# VS1063.net
KiCad netlist of a schematic drawn in Altium Designer
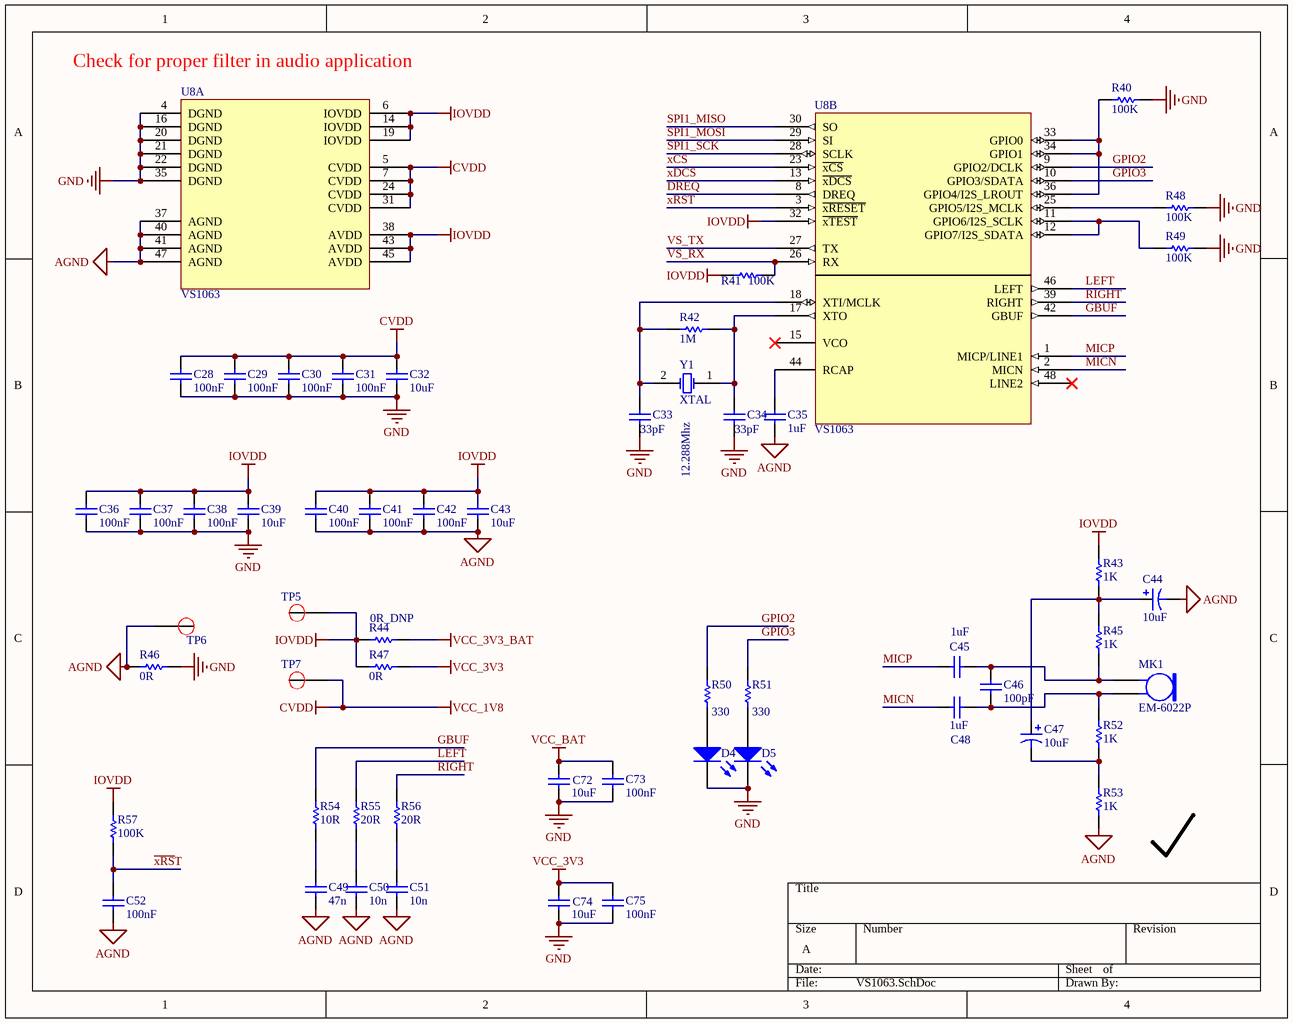
[diagram p0: VS1063.SchDoc]

(export (version "E")
  (design (tool "Eeschema 10.0.6"))
  (components
    (comp (ref "C28")
      (value "100nF")
      (footprint "0603PKG")
      (description "Capacitor (Semiconductor SIM Model)")
      (fields (field (name "Comment") "Cap Semi") (field (name "PUBLISHER") "Altium Limited"))
      (libsource (lib "Miscellaneous Devices") (part "Cap Semi"))
    )
    (comp (ref "C29")
      (value "100nF")
      (footprint "0603PKG")
      (description "Capacitor (Semiconductor SIM Model)")
      (fields (field (name "Comment") "Cap Semi") (field (name "PUBLISHER") "Altium Limited"))
      (libsource (lib "Miscellaneous Devices") (part "Cap Semi"))
    )
    (comp (ref "C30")
      (value "100nF")
      (footprint "0603PKG")
      (description "Capacitor (Semiconductor SIM Model)")
      (fields (field (name "Comment") "Cap Semi") (field (name "PUBLISHER") "Altium Limited"))
      (libsource (lib "Miscellaneous Devices") (part "Cap Semi"))
    )
    (comp (ref "C31")
      (value "100nF")
      (footprint "0603PKG")
      (description "Capacitor (Semiconductor SIM Model)")
      (fields (field (name "Comment") "Cap Semi") (field (name "PUBLISHER") "Altium Limited"))
      (libsource (lib "Miscellaneous Devices") (part "Cap Semi"))
    )
    (comp (ref "C32")
      (value "10uF")
      (footprint "0603PKG")
      (description "Capacitor (Semiconductor SIM Model)")
      (fields (field (name "Comment") "Cap Semi") (field (name "PUBLISHER") "Altium Limited"))
      (libsource (lib "Miscellaneous Devices") (part "Cap Semi"))
    )
    (comp (ref "C33")
      (value "33pF")
      (footprint "0603PKG")
      (description "Capacitor")
      (fields (field (name "Comment") "Cap") (field (name "PUBLISHER") "Altium Limited"))
      (libsource (lib "Miscellaneous Devices") (part "Cap"))
    )
    (comp (ref "C34")
      (value "33pF")
      (footprint "0603PKG")
      (description "Capacitor")
      (fields (field (name "Comment") "Cap") (field (name "PUBLISHER") "Altium Limited"))
      (libsource (lib "Miscellaneous Devices") (part "Cap"))
    )
    (comp (ref "C35")
      (value "1uF")
      (footprint "0603PKG")
      (description "Capacitor (Semiconductor SIM Model)")
      (fields (field (name "Comment") "Cap Semi") (field (name "PUBLISHER") "Altium Limited"))
      (libsource (lib "Miscellaneous Devices") (part "Cap Semi"))
    )
    (comp (ref "C36")
      (value "100nF")
      (footprint "0603PKG")
      (description "Capacitor (Semiconductor SIM Model)")
      (fields (field (name "Comment") "Cap Semi") (field (name "PUBLISHER") "Altium Limited"))
      (libsource (lib "Miscellaneous Devices") (part "Cap Semi"))
    )
    (comp (ref "C37")
      (value "100nF")
      (footprint "0603PKG")
      (description "Capacitor (Semiconductor SIM Model)")
      (fields (field (name "Comment") "Cap Semi") (field (name "PUBLISHER") "Altium Limited"))
      (libsource (lib "Miscellaneous Devices") (part "Cap Semi"))
    )
    (comp (ref "C38")
      (value "100nF")
      (footprint "0603PKG")
      (description "Capacitor (Semiconductor SIM Model)")
      (fields (field (name "Comment") "Cap Semi") (field (name "PUBLISHER") "Altium Limited"))
      (libsource (lib "Miscellaneous Devices") (part "Cap Semi"))
    )
    (comp (ref "C39")
      (value "10uF")
      (footprint "0603PKG")
      (description "Capacitor (Semiconductor SIM Model)")
      (fields (field (name "Comment") "Cap Semi") (field (name "PUBLISHER") "Altium Limited"))
      (libsource (lib "Miscellaneous Devices") (part "Cap Semi"))
    )
    (comp (ref "C40")
      (value "100nF")
      (footprint "0603PKG")
      (description "Capacitor (Semiconductor SIM Model)")
      (fields (field (name "Comment") "Cap Semi") (field (name "PUBLISHER") "Altium Limited"))
      (libsource (lib "Miscellaneous Devices") (part "Cap Semi"))
    )
    (comp (ref "C41")
      (value "100nF")
      (footprint "0603PKG")
      (description "Capacitor (Semiconductor SIM Model)")
      (fields (field (name "Comment") "Cap Semi") (field (name "PUBLISHER") "Altium Limited"))
      (libsource (lib "Miscellaneous Devices") (part "Cap Semi"))
    )
    (comp (ref "C42")
      (value "100nF")
      (footprint "0603PKG")
      (description "Capacitor (Semiconductor SIM Model)")
      (fields (field (name "Comment") "Cap Semi") (field (name "PUBLISHER") "Altium Limited"))
      (libsource (lib "Miscellaneous Devices") (part "Cap Semi"))
    )
    (comp (ref "C43")
      (value "10uF")
      (footprint "0603PKG")
      (description "Capacitor (Semiconductor SIM Model)")
      (fields (field (name "Comment") "Cap Semi") (field (name "PUBLISHER") "Altium Limited"))
      (libsource (lib "Miscellaneous Devices") (part "Cap Semi"))
    )
    (comp (ref "C44")
      (value "10uF")
      (footprint "3216X18N")
      (description "Polarized Capacitor (Surface Mount)")
      (fields (field (name "Comment") "Cap Pol3") (field (name "PUBLISHER") "Altium Limited"))
      (libsource (lib "Miscellaneous Devices") (part "Cap Pol3"))
    )
    (comp (ref "C45")
      (value "1uF")
      (footprint "0603PKG")
      (description "Capacitor (Semiconductor SIM Model)")
      (fields (field (name "Comment") "Cap Semi") (field (name "PUBLISHER") "Altium Limited"))
      (libsource (lib "Miscellaneous Devices") (part "Cap Semi"))
    )
    (comp (ref "C46")
      (value "100pF")
      (footprint "0603PKG")
      (description "Capacitor (Semiconductor SIM Model)")
      (fields (field (name "Comment") "Cap Semi") (field (name "PUBLISHER") "Altium Limited"))
      (libsource (lib "Miscellaneous Devices") (part "Cap Semi"))
    )
    (comp (ref "C47")
      (value "10uF")
      (footprint "3216X18N")
      (description "Polarized Capacitor (Surface Mount)")
      (fields (field (name "Comment") "Cap Pol3") (field (name "PUBLISHER") "Altium Limited"))
      (libsource (lib "Miscellaneous Devices") (part "Cap Pol3"))
    )
    (comp (ref "C48")
      (value "1uF")
      (footprint "0603PKG")
      (description "Capacitor (Semiconductor SIM Model)")
      (fields (field (name "Comment") "Cap Semi") (field (name "PUBLISHER") "Altium Limited"))
      (libsource (lib "Miscellaneous Devices") (part "Cap Semi"))
    )
    (comp (ref "C49")
      (value "47n")
      (footprint "C0805")
      (description "Capacitor (Semiconductor SIM Model)")
      (fields (field (name "Comment") "Cap Semi") (field (name "PUBLISHER") "Altium Limited"))
      (libsource (lib "Miscellaneous Devices") (part "Cap Semi"))
    )
    (comp (ref "C50")
      (value "10n")
      (footprint "C0805")
      (description "Capacitor (Semiconductor SIM Model)")
      (fields (field (name "Comment") "Cap Semi") (field (name "PUBLISHER") "Altium Limited"))
      (libsource (lib "Miscellaneous Devices") (part "Cap Semi"))
    )
    (comp (ref "C51")
      (value "10n")
      (footprint "C0805")
      (description "Capacitor (Semiconductor SIM Model)")
      (fields (field (name "Comment") "Cap Semi") (field (name "PUBLISHER") "Altium Limited"))
      (libsource (lib "Miscellaneous Devices") (part "Cap Semi"))
    )
    (comp (ref "C52")
      (value "100nF")
      (footprint "0603PKG")
      (description "Capacitor (Semiconductor SIM Model)")
      (fields (field (name "Comment") "Cap Semi") (field (name "PUBLISHER") "Altium Limited"))
      (libsource (lib "Miscellaneous Devices") (part "Cap Semi"))
    )
    (comp (ref "C72")
      (value "10uF")
      (footprint "C0805")
      (description "Capacitor (Semiconductor SIM Model)")
      (fields (field (name "Comment") "Cap Semi") (field (name "PUBLISHER") "Altium Limited"))
      (libsource (lib "Miscellaneous Devices") (part "Cap Semi"))
    )
    (comp (ref "C73")
      (value "100nF")
      (footprint "C0805")
      (description "Capacitor (Semiconductor SIM Model)")
      (fields (field (name "Comment") "Cap Semi") (field (name "PUBLISHER") "Altium Limited"))
      (libsource (lib "Miscellaneous Devices") (part "Cap Semi"))
    )
    (comp (ref "C74")
      (value "10uF")
      (footprint "C0805")
      (description "Capacitor (Semiconductor SIM Model)")
      (fields (field (name "Comment") "Cap Semi") (field (name "PUBLISHER") "Altium Limited"))
      (libsource (lib "Miscellaneous Devices") (part "Cap Semi"))
    )
    (comp (ref "C75")
      (value "100nF")
      (footprint "C0805")
      (description "Capacitor (Semiconductor SIM Model)")
      (fields (field (name "Comment") "Cap Semi") (field (name "PUBLISHER") "Altium Limited"))
      (libsource (lib "Miscellaneous Devices") (part "Cap Semi"))
    )
    (comp (ref "D4")
      (value "LED0")
      (footprint "C0805")
      (description "Typical INFRARED GaAs LED")
      (fields (field (name "PUBLISHER") "Altium Limited"))
      (libsource (lib "Miscellaneous Devices") (part "LED0"))
    )
    (comp (ref "D5")
      (value "LED0")
      (footprint "C0805")
      (description "Typical INFRARED GaAs LED")
      (fields (field (name "PUBLISHER") "Altium Limited"))
      (libsource (lib "Miscellaneous Devices") (part "LED0"))
    )
    (comp (ref "MK1")
      (value "EM-6022P")
      (footprint "Microphone")
      (description "Microphone")
      (fields (field (name "PUBLISHER") "Altium Limited"))
      (libsource (lib "Miscellaneous Devices") (part "Mic2"))
    )
    (comp (ref "R40")
      (value "100K")
      (footprint "0603PKG")
      (description "Resistor")
      (fields (field (name "Comment") "Res1") (field (name "PUBLISHER") "Altium Limited"))
      (libsource (lib "Miscellaneous Devices") (part "Res1"))
    )
    (comp (ref "R41")
      (value "100K")
      (footprint "0603PKG")
      (description "Resistor")
      (fields (field (name "Comment") "Res1") (field (name "PUBLISHER") "Altium Limited"))
      (libsource (lib "Miscellaneous Devices") (part "Res1"))
    )
    (comp (ref "R42")
      (value "1M")
      (footprint "0603PKG")
      (description "Resistor")
      (fields (field (name "Comment") "Res1") (field (name "PUBLISHER") "Altium Limited"))
      (libsource (lib "Miscellaneous Devices") (part "Res1"))
    )
    (comp (ref "R43")
      (value "1K")
      (footprint "0603PKG")
      (description "Resistor")
      (fields (field (name "Comment") "Res1") (field (name "PUBLISHER") "Altium Limited"))
      (libsource (lib "Miscellaneous Devices") (part "Res1"))
    )
    (comp (ref "R44")
      (value "0R_DNP")
      (footprint "0603PKG")
      (description "Resistor")
      (fields (field (name "Comment") "Res1") (field (name "PUBLISHER") "Altium Limited"))
      (libsource (lib "Miscellaneous Devices") (part "Res1"))
    )
    (comp (ref "R45")
      (value "1K")
      (footprint "0603PKG")
      (description "Resistor")
      (fields (field (name "Comment") "Res1") (field (name "PUBLISHER") "Altium Limited"))
      (libsource (lib "Miscellaneous Devices") (part "Res1"))
    )
    (comp (ref "R46")
      (value "0R")
      (footprint "0603PKG")
      (description "Resistor")
      (fields (field (name "Comment") "Res1") (field (name "PUBLISHER") "Altium Limited"))
      (libsource (lib "Miscellaneous Devices") (part "Res1"))
    )
    (comp (ref "R47")
      (value "0R")
      (footprint "0603PKG")
      (description "Resistor")
      (fields (field (name "Comment") "Res1") (field (name "PUBLISHER") "Altium Limited"))
      (libsource (lib "Miscellaneous Devices") (part "Res1"))
    )
    (comp (ref "R48")
      (value "100K")
      (footprint "0603PKG")
      (description "Resistor")
      (fields (field (name "Comment") "Res1") (field (name "PUBLISHER") "Altium Limited"))
      (libsource (lib "Miscellaneous Devices") (part "Res1"))
    )
    (comp (ref "R49")
      (value "100K")
      (footprint "0603PKG")
      (description "Resistor")
      (fields (field (name "Comment") "Res1") (field (name "PUBLISHER") "Altium Limited"))
      (libsource (lib "Miscellaneous Devices") (part "Res1"))
    )
    (comp (ref "R50")
      (value "330")
      (footprint "0603PKG")
      (description "Semiconductor Resistor")
      (fields (field (name "Comment") "Res Semi") (field (name "PUBLISHER") "Altium Limited"))
      (libsource (lib "Miscellaneous Devices") (part "Res Semi"))
    )
    (comp (ref "R51")
      (value "330")
      (footprint "0603PKG")
      (description "Semiconductor Resistor")
      (fields (field (name "Comment") "Res Semi") (field (name "PUBLISHER") "Altium Limited"))
      (libsource (lib "Miscellaneous Devices") (part "Res Semi"))
    )
    (comp (ref "R52")
      (value "1K")
      (footprint "0603PKG")
      (description "Resistor")
      (fields (field (name "Comment") "Res1") (field (name "PUBLISHER") "Altium Limited"))
      (libsource (lib "Miscellaneous Devices") (part "Res1"))
    )
    (comp (ref "R53")
      (value "1K")
      (footprint "0603PKG")
      (description "Resistor")
      (fields (field (name "Comment") "Res1") (field (name "PUBLISHER") "Altium Limited"))
      (libsource (lib "Miscellaneous Devices") (part "Res1"))
    )
    (comp (ref "R54")
      (value "10R")
      (footprint "C0805")
      (description "Resistor")
      (fields (field (name "Comment") "Res1") (field (name "PUBLISHER") "Altium Limited"))
      (libsource (lib "Miscellaneous Devices") (part "Res1"))
    )
    (comp (ref "R55")
      (value "20R")
      (footprint "C0805")
      (description "Resistor")
      (fields (field (name "Comment") "Res1") (field (name "PUBLISHER") "Altium Limited"))
      (libsource (lib "Miscellaneous Devices") (part "Res1"))
    )
    (comp (ref "R56")
      (value "20R")
      (footprint "C0805")
      (description "Resistor")
      (fields (field (name "Comment") "Res1") (field (name "PUBLISHER") "Altium Limited"))
      (libsource (lib "Miscellaneous Devices") (part "Res1"))
    )
    (comp (ref "R57")
      (value "100K")
      (footprint "0603PKG")
      (description "Resistor")
      (fields (field (name "Comment") "Res1") (field (name "PUBLISHER") "Altium Limited"))
      (libsource (lib "Miscellaneous Devices") (part "Res1"))
    )
    (comp (ref "TP5")
      (value "TP")
      (footprint "TP_15")
      (libsource (lib "Connector_IntLib") (part "Test Point"))
    )
    (comp (ref "TP6")
      (value "TP")
      (footprint "TP_15")
      (libsource (lib "Connector_IntLib") (part "Test Point"))
    )
    (comp (ref "TP7")
      (value "TP")
      (footprint "TP_15")
      (libsource (lib "Connector_IntLib") (part "Test Point"))
    )
    (comp (ref "U8")
      (value "VS1063")
      (footprint "LQFP48")
      (description "Audion Codec")
      (libsource (lib "Connector_IntLib") (part "VS1063"))
    )
    (comp (ref "Y1")
      (value "XTAL")
      (footprint "SMD_Crystal")
      (description "Crystal Oscillator")
      (fields (field (name "ALTIUM_VALUE") "12.288Mhz") (field (name "PUBLISHER") "Altium Limited"))
      (libsource (lib "Miscellaneous Devices") (part "XTAL"))
    )
  )
  (nets
    (net (code "1") (name "/DREQ") (class "Default")
      (node (ref "U8") (pin "8") (pinfunction "DREQ_8") (pintype "output"))
    )
    (net (code "2") (name "/GBUF") (class "Default")
      (node (ref "R54") (pin "1") (pinfunction "1_1") (pintype "passive"))
      (node (ref "U8") (pin "42") (pinfunction "GBUF_42") (pintype "output"))
    )
    (net (code "3") (name "/GPIO2") (class "Default")
      (node (ref "R50") (pin "2") (pinfunction "2_2") (pintype "passive"))
      (node (ref "U8") (pin "9") (pinfunction "GPIO2/DCLK_9") (pintype "bidirectional"))
    )
    (net (code "4") (name "/GPIO3") (class "Default")
      (node (ref "R51") (pin "2") (pinfunction "2_2") (pintype "passive"))
      (node (ref "U8") (pin "10") (pinfunction "GPIO3/SDATA_10") (pintype "bidirectional"))
    )
    (net (code "5") (name "/LEFT") (class "Default")
      (node (ref "R55") (pin "1") (pinfunction "1_1") (pintype "passive"))
      (node (ref "U8") (pin "46") (pinfunction "LEFT_46") (pintype "output"))
    )
    (net (code "6") (name "/MICN") (class "Default")
      (node (ref "C48") (pin "1") (pinfunction "1_1") (pintype "passive"))
      (node (ref "U8") (pin "2") (pinfunction "MICN_2") (pintype "input"))
    )
    (net (code "7") (name "/MICP") (class "Default")
      (node (ref "C45") (pin "1") (pinfunction "1_1") (pintype "passive"))
      (node (ref "U8") (pin "1") (pinfunction "MICP/LINE1_1") (pintype "input"))
    )
    (net (code "8") (name "/RIGHT") (class "Default")
      (node (ref "R56") (pin "1") (pinfunction "1_1") (pintype "passive"))
      (node (ref "U8") (pin "39") (pinfunction "RIGHT_39") (pintype "output"))
    )
    (net (code "9") (name "/SPI1_MISO") (class "Default")
      (node (ref "U8") (pin "30") (pinfunction "SO_30") (pintype "output"))
    )
    (net (code "10") (name "/SPI1_MOSI") (class "Default")
      (node (ref "U8") (pin "29") (pinfunction "SI_29") (pintype "input"))
    )
    (net (code "11") (name "/SPI1_SCK") (class "Default")
      (node (ref "U8") (pin "28") (pinfunction "SCLK_28") (pintype "bidirectional"))
    )
    (net (code "12") (name "/VS_RX") (class "Default")
      (node (ref "R41") (pin "1") (pinfunction "1_1") (pintype "passive"))
      (node (ref "U8") (pin "26") (pinfunction "RX_26") (pintype "input"))
    )
    (net (code "13") (name "/VS_TX") (class "Default")
      (node (ref "U8") (pin "27") (pinfunction "TX_27") (pintype "output"))
    )
    (net (code "14") (name "/~{xCS}") (class "Default")
      (node (ref "U8") (pin "23") (pinfunction "~{xCS}_23") (pintype "input"))
    )
    (net (code "15") (name "/~{xDCS}") (class "Default")
      (node (ref "U8") (pin "13") (pinfunction "~{xDCS}_13") (pintype "input"))
    )
    (net (code "16") (name "/~{xRS}T") (class "Default")
      (node (ref "C52") (pin "1") (pinfunction "1_1") (pintype "passive"))
      (node (ref "R57") (pin "2") (pinfunction "2_2") (pintype "passive"))
      (node (ref "U8") (pin "3") (pinfunction "~{xRESET}_3") (pintype "input"))
    )
    (net (code "17") (name "AGND") (class "Default")
      (node (ref "C35") (pin "1") (pinfunction "1_1") (pintype "passive"))
      (node (ref "C40") (pin "1") (pinfunction "1_1") (pintype "passive"))
      (node (ref "C41") (pin "1") (pinfunction "1_1") (pintype "passive"))
      (node (ref "C42") (pin "1") (pinfunction "1_1") (pintype "passive"))
      (node (ref "C43") (pin "1") (pinfunction "1_1") (pintype "passive"))
      (node (ref "C44") (pin "2") (pinfunction "2_2") (pintype "passive"))
      (node (ref "C49") (pin "2") (pinfunction "2_2") (pintype "passive"))
      (node (ref "C50") (pin "2") (pinfunction "2_2") (pintype "passive"))
      (node (ref "C51") (pin "2") (pinfunction "2_2") (pintype "passive"))
      (node (ref "C52") (pin "2") (pinfunction "2_2") (pintype "passive"))
      (node (ref "R46") (pin "2") (pinfunction "2_2") (pintype "passive"))
      (node (ref "R53") (pin "2") (pinfunction "2_2") (pintype "passive"))
      (node (ref "TP6") (pin "1") (pinfunction "1_1") (pintype "passive"))
      (node (ref "U8") (pin "37") (pinfunction "AGND_37") (pintype "power_in"))
      (node (ref "U8") (pin "40") (pinfunction "AGND_40") (pintype "power_in"))
      (node (ref "U8") (pin "41") (pinfunction "AGND_41") (pintype "power_in"))
      (node (ref "U8") (pin "47") (pinfunction "AGND_47") (pintype "power_in"))
    )
    (net (code "18") (name "CVDD") (class "Default")
      (node (ref "C28") (pin "2") (pinfunction "2_2") (pintype "passive"))
      (node (ref "C29") (pin "2") (pinfunction "2_2") (pintype "passive"))
      (node (ref "C30") (pin "2") (pinfunction "2_2") (pintype "passive"))
      (node (ref "C31") (pin "2") (pinfunction "2_2") (pintype "passive"))
      (node (ref "C32") (pin "2") (pinfunction "2_2") (pintype "passive"))
      (node (ref "TP7") (pin "1") (pinfunction "1_1") (pintype "passive"))
      (node (ref "U8") (pin "24") (pinfunction "CVDD_24") (pintype "power_in"))
      (node (ref "U8") (pin "31") (pinfunction "CVDD_31") (pintype "power_in"))
      (node (ref "U8") (pin "5") (pinfunction "CVDD_5") (pintype "power_in"))
      (node (ref "U8") (pin "7") (pinfunction "CVDD_7") (pintype "power_in"))
    )
    (net (code "19") (name "GND") (class "Default")
      (node (ref "C28") (pin "1") (pinfunction "1_1") (pintype "passive"))
      (node (ref "C29") (pin "1") (pinfunction "1_1") (pintype "passive"))
      (node (ref "C30") (pin "1") (pinfunction "1_1") (pintype "passive"))
      (node (ref "C31") (pin "1") (pinfunction "1_1") (pintype "passive"))
      (node (ref "C32") (pin "1") (pinfunction "1_1") (pintype "passive"))
      (node (ref "C33") (pin "1") (pinfunction "1_1") (pintype "passive"))
      (node (ref "C34") (pin "1") (pinfunction "1_1") (pintype "passive"))
      (node (ref "C36") (pin "1") (pinfunction "1_1") (pintype "passive"))
      (node (ref "C37") (pin "1") (pinfunction "1_1") (pintype "passive"))
      (node (ref "C38") (pin "1") (pinfunction "1_1") (pintype "passive"))
      (node (ref "C39") (pin "1") (pinfunction "1_1") (pintype "passive"))
      (node (ref "C72") (pin "1") (pinfunction "1_1") (pintype "passive"))
      (node (ref "C73") (pin "1") (pinfunction "1_1") (pintype "passive"))
      (node (ref "C74") (pin "1") (pinfunction "1_1") (pintype "passive"))
      (node (ref "C75") (pin "1") (pinfunction "1_1") (pintype "passive"))
      (node (ref "D4") (pin "2") (pinfunction "K_2") (pintype "passive"))
      (node (ref "D5") (pin "2") (pinfunction "K_2") (pintype "passive"))
      (node (ref "R40") (pin "1") (pinfunction "1_1") (pintype "passive"))
      (node (ref "R46") (pin "1") (pinfunction "1_1") (pintype "passive"))
      (node (ref "R48") (pin "1") (pinfunction "1_1") (pintype "passive"))
      (node (ref "R49") (pin "1") (pinfunction "1_1") (pintype "passive"))
      (node (ref "U8") (pin "16") (pinfunction "DGND_16") (pintype "power_in"))
      (node (ref "U8") (pin "20") (pinfunction "DGND_20") (pintype "power_in"))
      (node (ref "U8") (pin "21") (pinfunction "DGND_21") (pintype "power_in"))
      (node (ref "U8") (pin "22") (pinfunction "DGND_22") (pintype "power_in"))
      (node (ref "U8") (pin "35") (pinfunction "DGND_35") (pintype "power_in"))
      (node (ref "U8") (pin "4") (pinfunction "DGND_4") (pintype "power_in"))
    )
    (net (code "20") (name "IOVDD") (class "Default")
      (node (ref "C36") (pin "2") (pinfunction "2_2") (pintype "passive"))
      (node (ref "C37") (pin "2") (pinfunction "2_2") (pintype "passive"))
      (node (ref "C38") (pin "2") (pinfunction "2_2") (pintype "passive"))
      (node (ref "C39") (pin "2") (pinfunction "2_2") (pintype "passive"))
      (node (ref "C40") (pin "2") (pinfunction "2_2") (pintype "passive"))
      (node (ref "C41") (pin "2") (pinfunction "2_2") (pintype "passive"))
      (node (ref "C42") (pin "2") (pinfunction "2_2") (pintype "passive"))
      (node (ref "C43") (pin "2") (pinfunction "2_2") (pintype "passive"))
      (node (ref "R41") (pin "2") (pinfunction "2_2") (pintype "passive"))
      (node (ref "R43") (pin "1") (pinfunction "1_1") (pintype "passive"))
      (node (ref "R44") (pin "2") (pinfunction "2_2") (pintype "passive"))
      (node (ref "R47") (pin "2") (pinfunction "2_2") (pintype "passive"))
      (node (ref "R57") (pin "1") (pinfunction "1_1") (pintype "passive"))
      (node (ref "TP5") (pin "1") (pinfunction "1_1") (pintype "passive"))
      (node (ref "U8") (pin "14") (pinfunction "IOVDD_14") (pintype "power_in"))
      (node (ref "U8") (pin "19") (pinfunction "IOVDD_19") (pintype "power_in"))
      (node (ref "U8") (pin "32") (pinfunction "~{xTEST}_32") (pintype "input"))
      (node (ref "U8") (pin "38") (pinfunction "AVDD_38") (pintype "power_in"))
      (node (ref "U8") (pin "43") (pinfunction "AVDD_43") (pintype "power_in"))
      (node (ref "U8") (pin "45") (pinfunction "AVDD_45") (pintype "power_in"))
      (node (ref "U8") (pin "6") (pinfunction "IOVDD_6") (pintype "power_in"))
    )
    (net (code "21") (name "Net-(C44-Pad1)") (class "Default")
      (node (ref "C44") (pin "1") (pinfunction "1_1") (pintype "passive"))
      (node (ref "C47") (pin "1") (pinfunction "1_1") (pintype "passive"))
      (node (ref "R43") (pin "2") (pinfunction "2_2") (pintype "passive"))
      (node (ref "R45") (pin "1") (pinfunction "1_1") (pintype "passive"))
    )
    (net (code "22") (name "Net-(C45-Pad2)") (class "Default")
      (node (ref "C45") (pin "2") (pinfunction "2_2") (pintype "passive"))
      (node (ref "C46") (pin "2") (pinfunction "2_2") (pintype "passive"))
      (node (ref "MK1") (pin "1") (pinfunction "1_1") (pintype "passive"))
      (node (ref "R45") (pin "2") (pinfunction "2_2") (pintype "passive"))
    )
    (net (code "23") (name "Net-(C46-Pad1)") (class "Default")
      (node (ref "C46") (pin "1") (pinfunction "1_1") (pintype "passive"))
      (node (ref "C48") (pin "2") (pinfunction "2_2") (pintype "passive"))
      (node (ref "MK1") (pin "2") (pinfunction "2_2") (pintype "passive"))
      (node (ref "R52") (pin "1") (pinfunction "1_1") (pintype "passive"))
    )
    (net (code "24") (name "Net-(C47-Pad2)") (class "Default")
      (node (ref "C47") (pin "2") (pinfunction "2_2") (pintype "passive"))
      (node (ref "R52") (pin "2") (pinfunction "2_2") (pintype "passive"))
      (node (ref "R53") (pin "1") (pinfunction "1_1") (pintype "passive"))
    )
    (net (code "25") (name "Net-(C49-Pad1)") (class "Default")
      (node (ref "C49") (pin "1") (pinfunction "1_1") (pintype "passive"))
      (node (ref "R54") (pin "2") (pinfunction "2_2") (pintype "passive"))
    )
    (net (code "26") (name "Net-(C50-Pad1)") (class "Default")
      (node (ref "C50") (pin "1") (pinfunction "1_1") (pintype "passive"))
      (node (ref "R55") (pin "2") (pinfunction "2_2") (pintype "passive"))
    )
    (net (code "27") (name "Net-(C51-Pad1)") (class "Default")
      (node (ref "C51") (pin "1") (pinfunction "1_1") (pintype "passive"))
      (node (ref "R56") (pin "2") (pinfunction "2_2") (pintype "passive"))
    )
    (net (code "28") (name "Net-(D4-A)") (class "Default")
      (node (ref "D4") (pin "1") (pinfunction "A_1") (pintype "passive"))
      (node (ref "R50") (pin "1") (pinfunction "1_1") (pintype "passive"))
    )
    (net (code "29") (name "Net-(D5-A)") (class "Default")
      (node (ref "D5") (pin "1") (pinfunction "A_1") (pintype "passive"))
      (node (ref "R51") (pin "1") (pinfunction "1_1") (pintype "passive"))
    )
    (net (code "30") (name "Net-(U8B-GPIO0)") (class "Default")
      (node (ref "R40") (pin "2") (pinfunction "2_2") (pintype "passive"))
      (node (ref "U8") (pin "33") (pinfunction "GPIO0_33") (pintype "bidirectional"))
      (node (ref "U8") (pin "34") (pinfunction "GPIO1_34") (pintype "bidirectional"))
      (node (ref "U8") (pin "36") (pinfunction "GPIO4/I2S_LROUT_36") (pintype "bidirectional"))
    )
    (net (code "31") (name "Net-(U8B-GPIO5{slash}I2S_MCLK)") (class "Default")
      (node (ref "R48") (pin "2") (pinfunction "2_2") (pintype "passive"))
      (node (ref "U8") (pin "25") (pinfunction "GPIO5/I2S_MCLK_25") (pintype "bidirectional"))
    )
    (net (code "32") (name "Net-(U8B-GPIO6{slash}I2S_SCLK)") (class "Default")
      (node (ref "R49") (pin "2") (pinfunction "2_2") (pintype "passive"))
      (node (ref "U8") (pin "11") (pinfunction "GPIO6/I2S_SCLK_11") (pintype "bidirectional"))
      (node (ref "U8") (pin "12") (pinfunction "GPIO7/I2S_SDATA_12") (pintype "bidirectional"))
    )
    (net (code "33") (name "Net-(U8B-RCAP)") (class "Default")
      (node (ref "C35") (pin "2") (pinfunction "2_2") (pintype "passive"))
      (node (ref "U8") (pin "44") (pinfunction "RCAP_44") (pintype "passive"))
    )
    (net (code "34") (name "Net-(U8B-XTI{slash}MCLK)") (class "Default")
      (node (ref "C33") (pin "2") (pinfunction "2_2") (pintype "passive"))
      (node (ref "R42") (pin "2") (pinfunction "2_2") (pintype "passive"))
      (node (ref "U8") (pin "18") (pinfunction "XTI/MCLK_18") (pintype "bidirectional"))
      (node (ref "Y1") (pin "2") (pinfunction "OSC2_2") (pintype "passive"))
    )
    (net (code "35") (name "Net-(U8B-XTO)") (class "Default")
      (node (ref "C34") (pin "2") (pinfunction "2_2") (pintype "passive"))
      (node (ref "R42") (pin "1") (pinfunction "1_1") (pintype "passive"))
      (node (ref "U8") (pin "17") (pinfunction "XTO_17") (pintype "output"))
      (node (ref "Y1") (pin "1") (pinfunction "OSC1_1") (pintype "passive"))
    )
    (net (code "36") (name "VCC_3V3") (class "Default")
      (node (ref "C74") (pin "2") (pinfunction "2_2") (pintype "passive"))
      (node (ref "C75") (pin "2") (pinfunction "2_2") (pintype "passive"))
      (node (ref "R47") (pin "1") (pinfunction "1_1") (pintype "passive"))
    )
    (net (code "37") (name "VCC_3V3_BAT") (class "Default")
      (node (ref "R44") (pin "1") (pinfunction "1_1") (pintype "passive"))
    )
    (net (code "38") (name "VCC_BAT") (class "Default")
      (node (ref "C72") (pin "2") (pinfunction "2_2") (pintype "passive"))
      (node (ref "C73") (pin "2") (pinfunction "2_2") (pintype "passive"))
    )
    (net (code "39") (name "unconnected-(U8B-LINE2-Pad48)") (class "Default")
      (node (ref "U8") (pin "48") (pinfunction "LINE2_48") (pintype "input+no_connect"))
    )
    (net (code "40") (name "unconnected-(U8B-VCO-Pad15)") (class "Default")
      (node (ref "U8") (pin "15") (pinfunction "VCO_15") (pintype "passive+no_connect"))
    )
  )
)
